# Cross.net
KiCad netlist of a schematic drawn in Altium Designer
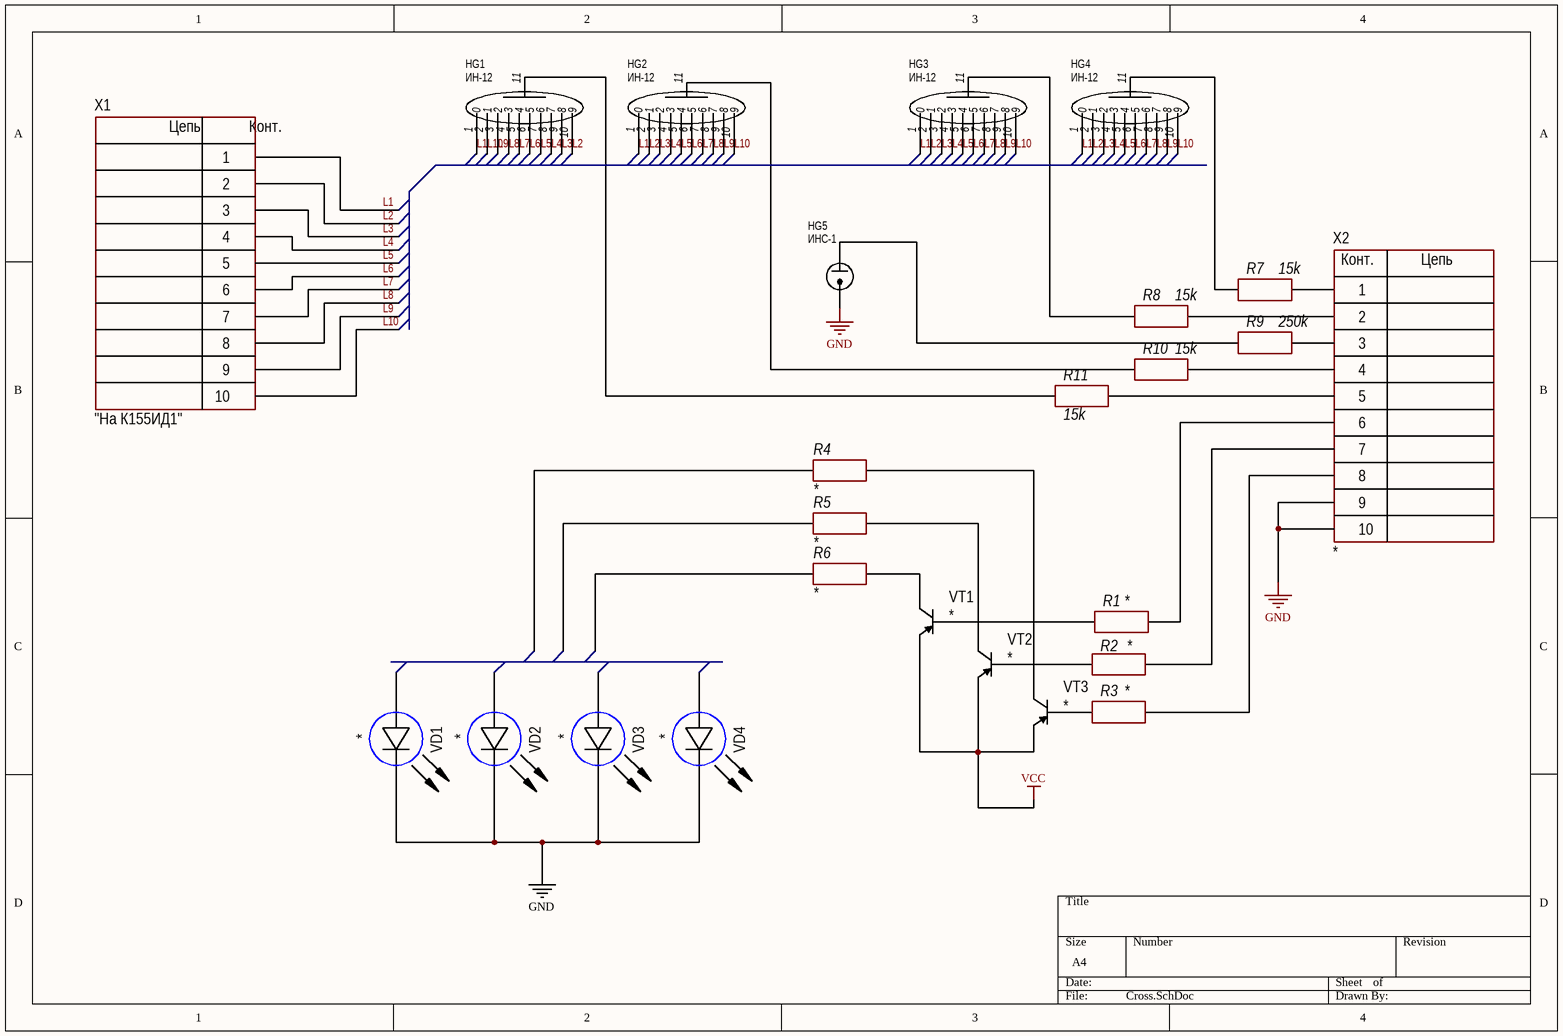
[diagram p0: Cross.SchDoc]

(export (version "E")
  (design (tool "Eeschema 10.0.6"))
  (components
    (comp (ref "HG1") (value "ИН-12") (footprint "PCBComponent_1") (libsource (lib "IN-12") (part "IN-12")))
    (comp (ref "HG2") (value "ИН-12") (footprint "PCBComponent_1") (libsource (lib "IN-12") (part "IN-12")))
    (comp (ref "HG3") (value "ИН-12") (footprint "PCBComponent_1") (libsource (lib "IN-12") (part "IN-12")))
    (comp (ref "HG4") (value "ИН-12") (footprint "PCBComponent_1") (libsource (lib "IN-12") (part "IN-12")))
    (comp (ref "HG5") (value "ИНС-1") (footprint "ИНС-1") (libsource (lib "ИНС-1") (part "ИНС-1")))
    (comp (ref "R1")
      (value "*")
      (footprint "MLT")
      (description "MLT")
      (libsource (lib "Resistor_MLT") (part "Resistor"))
    )
    (comp (ref "R2")
      (value "*")
      (footprint "MLT")
      (description "MLT")
      (libsource (lib "Resistor_MLT") (part "Resistor"))
    )
    (comp (ref "R3")
      (value "*")
      (footprint "MLT")
      (description "MLT")
      (libsource (lib "Resistor_MLT") (part "Resistor"))
    )
    (comp (ref "R4")
      (value "*")
      (footprint "MLT")
      (description "MLT")
      (libsource (lib "Resistor_MLT") (part "Resistor"))
    )
    (comp (ref "R5")
      (value "*")
      (footprint "MLT")
      (description "MLT")
      (libsource (lib "Resistor_MLT") (part "Resistor"))
    )
    (comp (ref "R6")
      (value "*")
      (footprint "MLT")
      (description "MLT")
      (libsource (lib "Resistor_MLT") (part "Resistor"))
    )
    (comp (ref "R7")
      (value "15k")
      (footprint "MLT")
      (description "MLT")
      (libsource (lib "Resistor_MLT") (part "Resistor"))
    )
    (comp (ref "R8")
      (value "15k")
      (footprint "MLT")
      (description "MLT")
      (libsource (lib "Resistor_MLT") (part "Resistor"))
    )
    (comp (ref "R9")
      (value "250k")
      (footprint "MLT")
      (description "MLT")
      (libsource (lib "") (part "Resistor_1"))
    )
    (comp (ref "R10")
      (value "15k")
      (footprint "MLT")
      (description "MLT")
      (libsource (lib "Resistor_MLT") (part "Resistor"))
    )
    (comp (ref "R11")
      (value "15k")
      (footprint "MLT")
      (description "MLT")
      (libsource (lib "Resistor_MLT") (part "Resistor"))
    )
    (comp (ref "VD1") (value "*") (footprint "CH1206LY") (libsource (lib "Discrete") (part "LED")))
    (comp (ref "VD2") (value "*") (footprint "CH1206LY") (libsource (lib "Discrete") (part "LED")))
    (comp (ref "VD3") (value "*") (footprint "CH1206LY") (libsource (lib "Discrete") (part "LED")))
    (comp (ref "VD4") (value "*") (footprint "CH1206LY") (libsource (lib "Discrete") (part "LED")))
    (comp (ref "VT1")
      (value "*")
      (footprint "TO220_123")
      (description "Bipolar")
      (libsource (lib "Transistor") (part "PNP"))
    )
    (comp (ref "VT2")
      (value "*")
      (footprint "TO220_123")
      (description "Bipolar")
      (libsource (lib "Transistor") (part "PNP"))
    )
    (comp (ref "VT3")
      (value "*")
      (footprint "TO220_123")
      (description "Bipolar")
      (libsource (lib "Transistor") (part "PNP"))
    )
    (comp (ref "X1")
      (value "\"На К155ИД1\"")
      (footprint "CON: PLS-10")
      (libsource (lib "") (part "10-Connector_1"))
    )
    (comp (ref "X2")
      (value "*")
      (footprint "CON: PLS-10")
      (libsource (lib "Connectors") (part "10-Connector"))
    )
  )
  (nets
    (net (code "1") (name "/L1") (class "Default")
      (node (ref "HG1") (pin "1") (pinfunction "0_1") (pintype "passive"))
      (node (ref "HG2") (pin "1") (pinfunction "0_1") (pintype "passive"))
      (node (ref "HG3") (pin "1") (pinfunction "0_1") (pintype "passive"))
      (node (ref "HG4") (pin "1") (pinfunction "0_1") (pintype "passive"))
      (node (ref "X1") (pin "1") (pinfunction "1_1") (pintype "passive"))
    )
    (net (code "2") (name "/L2") (class "Default")
      (node (ref "HG1") (pin "10") (pinfunction "9_10") (pintype "passive"))
      (node (ref "HG2") (pin "2") (pinfunction "1_2") (pintype "passive"))
      (node (ref "HG3") (pin "2") (pinfunction "1_2") (pintype "passive"))
      (node (ref "HG4") (pin "2") (pinfunction "1_2") (pintype "passive"))
      (node (ref "X1") (pin "2") (pinfunction "2_2") (pintype "passive"))
    )
    (net (code "3") (name "/L3") (class "Default")
      (node (ref "HG1") (pin "9") (pinfunction "8_9") (pintype "passive"))
      (node (ref "HG2") (pin "3") (pinfunction "2_3") (pintype "passive"))
      (node (ref "HG3") (pin "3") (pinfunction "2_3") (pintype "passive"))
      (node (ref "HG4") (pin "3") (pinfunction "2_3") (pintype "passive"))
      (node (ref "X1") (pin "3") (pinfunction "3_3") (pintype "power_in"))
    )
    (net (code "4") (name "/L4") (class "Default")
      (node (ref "HG1") (pin "8") (pinfunction "7_8") (pintype "passive"))
      (node (ref "HG2") (pin "4") (pinfunction "3_4") (pintype "passive"))
      (node (ref "HG3") (pin "4") (pinfunction "3_4") (pintype "passive"))
      (node (ref "HG4") (pin "4") (pinfunction "3_4") (pintype "passive"))
      (node (ref "X1") (pin "4") (pinfunction "4_4") (pintype "power_in"))
    )
    (net (code "5") (name "/L5") (class "Default")
      (node (ref "HG1") (pin "7") (pinfunction "6_7") (pintype "passive"))
      (node (ref "HG2") (pin "5") (pinfunction "4_5") (pintype "passive"))
      (node (ref "HG3") (pin "5") (pinfunction "4_5") (pintype "passive"))
      (node (ref "HG4") (pin "5") (pinfunction "4_5") (pintype "passive"))
      (node (ref "X1") (pin "5") (pinfunction "5_5") (pintype "power_in"))
    )
    (net (code "6") (name "/L6") (class "Default")
      (node (ref "HG1") (pin "6") (pinfunction "5_6") (pintype "passive"))
      (node (ref "HG2") (pin "6") (pinfunction "5_6") (pintype "passive"))
      (node (ref "HG3") (pin "6") (pinfunction "5_6") (pintype "passive"))
      (node (ref "HG4") (pin "6") (pinfunction "5_6") (pintype "passive"))
      (node (ref "X1") (pin "6") (pinfunction "6_6") (pintype "power_in"))
    )
    (net (code "7") (name "/L7") (class "Default")
      (node (ref "HG1") (pin "5") (pinfunction "4_5") (pintype "passive"))
      (node (ref "HG2") (pin "7") (pinfunction "6_7") (pintype "passive"))
      (node (ref "HG3") (pin "7") (pinfunction "6_7") (pintype "passive"))
      (node (ref "HG4") (pin "7") (pinfunction "6_7") (pintype "passive"))
      (node (ref "X1") (pin "7") (pinfunction "7_7") (pintype "power_in"))
    )
    (net (code "8") (name "/L8") (class "Default")
      (node (ref "HG1") (pin "4") (pinfunction "3_4") (pintype "passive"))
      (node (ref "HG2") (pin "8") (pinfunction "7_8") (pintype "passive"))
      (node (ref "HG3") (pin "8") (pinfunction "7_8") (pintype "passive"))
      (node (ref "HG4") (pin "8") (pinfunction "7_8") (pintype "passive"))
      (node (ref "X1") (pin "8") (pinfunction "8_8") (pintype "power_in"))
    )
    (net (code "9") (name "/L9") (class "Default")
      (node (ref "HG1") (pin "3") (pinfunction "2_3") (pintype "passive"))
      (node (ref "HG2") (pin "9") (pinfunction "8_9") (pintype "passive"))
      (node (ref "HG3") (pin "9") (pinfunction "8_9") (pintype "passive"))
      (node (ref "HG4") (pin "9") (pinfunction "8_9") (pintype "passive"))
      (node (ref "X1") (pin "9") (pinfunction "9_9") (pintype "power_in"))
    )
    (net (code "10") (name "/L10") (class "Default")
      (node (ref "HG1") (pin "2") (pinfunction "1_2") (pintype "passive"))
      (node (ref "HG2") (pin "10") (pinfunction "9_10") (pintype "passive"))
      (node (ref "HG3") (pin "10") (pinfunction "9_10") (pintype "passive"))
      (node (ref "HG4") (pin "10") (pinfunction "9_10") (pintype "passive"))
      (node (ref "X1") (pin "10") (pinfunction "10_10") (pintype "power_in"))
    )
    (net (code "11") (name "GND") (class "Default")
      (node (ref "HG5") (pin "1") (pinfunction "21_1") (pintype "passive"))
      (node (ref "VD1") (pin "2") (pinfunction "C_2") (pintype "passive"))
      (node (ref "VD2") (pin "2") (pinfunction "C_2") (pintype "passive"))
      (node (ref "VD3") (pin "2") (pinfunction "C_2") (pintype "passive"))
      (node (ref "VD4") (pin "2") (pinfunction "C_2") (pintype "passive"))
      (node (ref "X2") (pin "10") (pinfunction "10_10") (pintype "power_in"))
      (node (ref "X2") (pin "9") (pinfunction "9_9") (pintype "power_in"))
    )
    (net (code "12") (name "Net-(HG1-Pad11)") (class "Default")
      (node (ref "HG1") (pin "11") (pinfunction "11_11") (pintype "passive"))
      (node (ref "R11") (pin "1") (pintype "passive"))
    )
    (net (code "13") (name "Net-(HG2-Pad11)") (class "Default")
      (node (ref "HG2") (pin "11") (pinfunction "11_11") (pintype "passive"))
      (node (ref "R10") (pin "1") (pintype "passive"))
    )
    (net (code "14") (name "Net-(HG3-Pad11)") (class "Default")
      (node (ref "HG3") (pin "11") (pinfunction "11_11") (pintype "passive"))
      (node (ref "R8") (pin "1") (pintype "passive"))
    )
    (net (code "15") (name "Net-(HG4-Pad11)") (class "Default")
      (node (ref "HG4") (pin "11") (pinfunction "11_11") (pintype "passive"))
      (node (ref "R7") (pin "1") (pintype "passive"))
    )
    (net (code "16") (name "Net-(HG5-Pad2)") (class "Default")
      (node (ref "HG5") (pin "2") (pinfunction "2_2") (pintype "passive"))
      (node (ref "R9") (pin "1") (pintype "passive"))
    )
    (net (code "17") (name "Net-(R1-Pad2)") (class "Default")
      (node (ref "R1") (pin "2") (pintype "passive"))
      (node (ref "X2") (pin "6") (pinfunction "6_6") (pintype "power_in"))
    )
    (net (code "18") (name "Net-(R2-Pad2)") (class "Default")
      (node (ref "R2") (pin "2") (pintype "passive"))
      (node (ref "X2") (pin "7") (pinfunction "7_7") (pintype "power_in"))
    )
    (net (code "19") (name "Net-(R3-Pad2)") (class "Default")
      (node (ref "R3") (pin "2") (pintype "passive"))
      (node (ref "X2") (pin "8") (pinfunction "8_8") (pintype "power_in"))
    )
    (net (code "20") (name "Net-(R7-Pad2)") (class "Default")
      (node (ref "R7") (pin "2") (pintype "passive"))
      (node (ref "X2") (pin "1") (pinfunction "1_1") (pintype "passive"))
    )
    (net (code "21") (name "Net-(R8-Pad2)") (class "Default")
      (node (ref "R8") (pin "2") (pintype "passive"))
      (node (ref "X2") (pin "2") (pinfunction "2_2") (pintype "passive"))
    )
    (net (code "22") (name "Net-(R9-Pad2)") (class "Default")
      (node (ref "R9") (pin "2") (pintype "passive"))
      (node (ref "X2") (pin "3") (pinfunction "3_3") (pintype "power_in"))
    )
    (net (code "23") (name "Net-(R10-Pad2)") (class "Default")
      (node (ref "R10") (pin "2") (pintype "passive"))
      (node (ref "X2") (pin "4") (pinfunction "4_4") (pintype "power_in"))
    )
    (net (code "24") (name "Net-(R11-Pad2)") (class "Default")
      (node (ref "R11") (pin "2") (pintype "passive"))
      (node (ref "X2") (pin "5") (pinfunction "5_5") (pintype "power_in"))
    )
    (net (code "25") (name "Net-(VT1-B)") (class "Default")
      (node (ref "R1") (pin "1") (pintype "passive"))
      (node (ref "VT1") (pin "1") (pinfunction "B_1") (pintype "passive"))
    )
    (net (code "26") (name "Net-(VT1-C)") (class "Default")
      (node (ref "R6") (pin "2") (pintype "passive"))
      (node (ref "VT1") (pin "3") (pinfunction "C_3") (pintype "passive"))
    )
    (net (code "27") (name "Net-(VT2-B)") (class "Default")
      (node (ref "R2") (pin "1") (pintype "passive"))
      (node (ref "VT2") (pin "1") (pinfunction "B_1") (pintype "passive"))
    )
    (net (code "28") (name "Net-(VT2-C)") (class "Default")
      (node (ref "R5") (pin "2") (pintype "passive"))
      (node (ref "VT2") (pin "3") (pinfunction "C_3") (pintype "passive"))
    )
    (net (code "29") (name "Net-(VT3-B)") (class "Default")
      (node (ref "R3") (pin "1") (pintype "passive"))
      (node (ref "VT3") (pin "1") (pinfunction "B_1") (pintype "passive"))
    )
    (net (code "30") (name "Net-(VT3-C)") (class "Default")
      (node (ref "R4") (pin "2") (pintype "passive"))
      (node (ref "VT3") (pin "3") (pinfunction "C_3") (pintype "passive"))
    )
    (net (code "31") (name "VCC") (class "Default")
      (node (ref "VT1") (pin "2") (pinfunction "E_2") (pintype "passive"))
      (node (ref "VT2") (pin "2") (pinfunction "E_2") (pintype "passive"))
      (node (ref "VT3") (pin "2") (pinfunction "E_2") (pintype "passive"))
    )
    (net (code "32") (name "unconnected-(R4-Pad1)") (class "Default")
      (node (ref "R4") (pin "1") (pintype "passive"))
    )
    (net (code "33") (name "unconnected-(R5-Pad1)") (class "Default")
      (node (ref "R5") (pin "1") (pintype "passive"))
    )
    (net (code "34") (name "unconnected-(R6-Pad1)") (class "Default")
      (node (ref "R6") (pin "1") (pintype "passive"))
    )
    (net (code "35") (name "unconnected-(VD1-A-Pad1)") (class "Default")
      (node (ref "VD1") (pin "1") (pinfunction "A_1") (pintype "passive"))
    )
    (net (code "36") (name "unconnected-(VD2-A-Pad1)") (class "Default")
      (node (ref "VD2") (pin "1") (pinfunction "A_1") (pintype "passive"))
    )
    (net (code "37") (name "unconnected-(VD3-A-Pad1)") (class "Default")
      (node (ref "VD3") (pin "1") (pinfunction "A_1") (pintype "passive"))
    )
    (net (code "38") (name "unconnected-(VD4-A-Pad1)") (class "Default")
      (node (ref "VD4") (pin "1") (pinfunction "A_1") (pintype "passive"))
    )
  )
)
